# Qwiic_Iridium_9603N.net
KiCad netlist of a schematic drawn in EAGLE
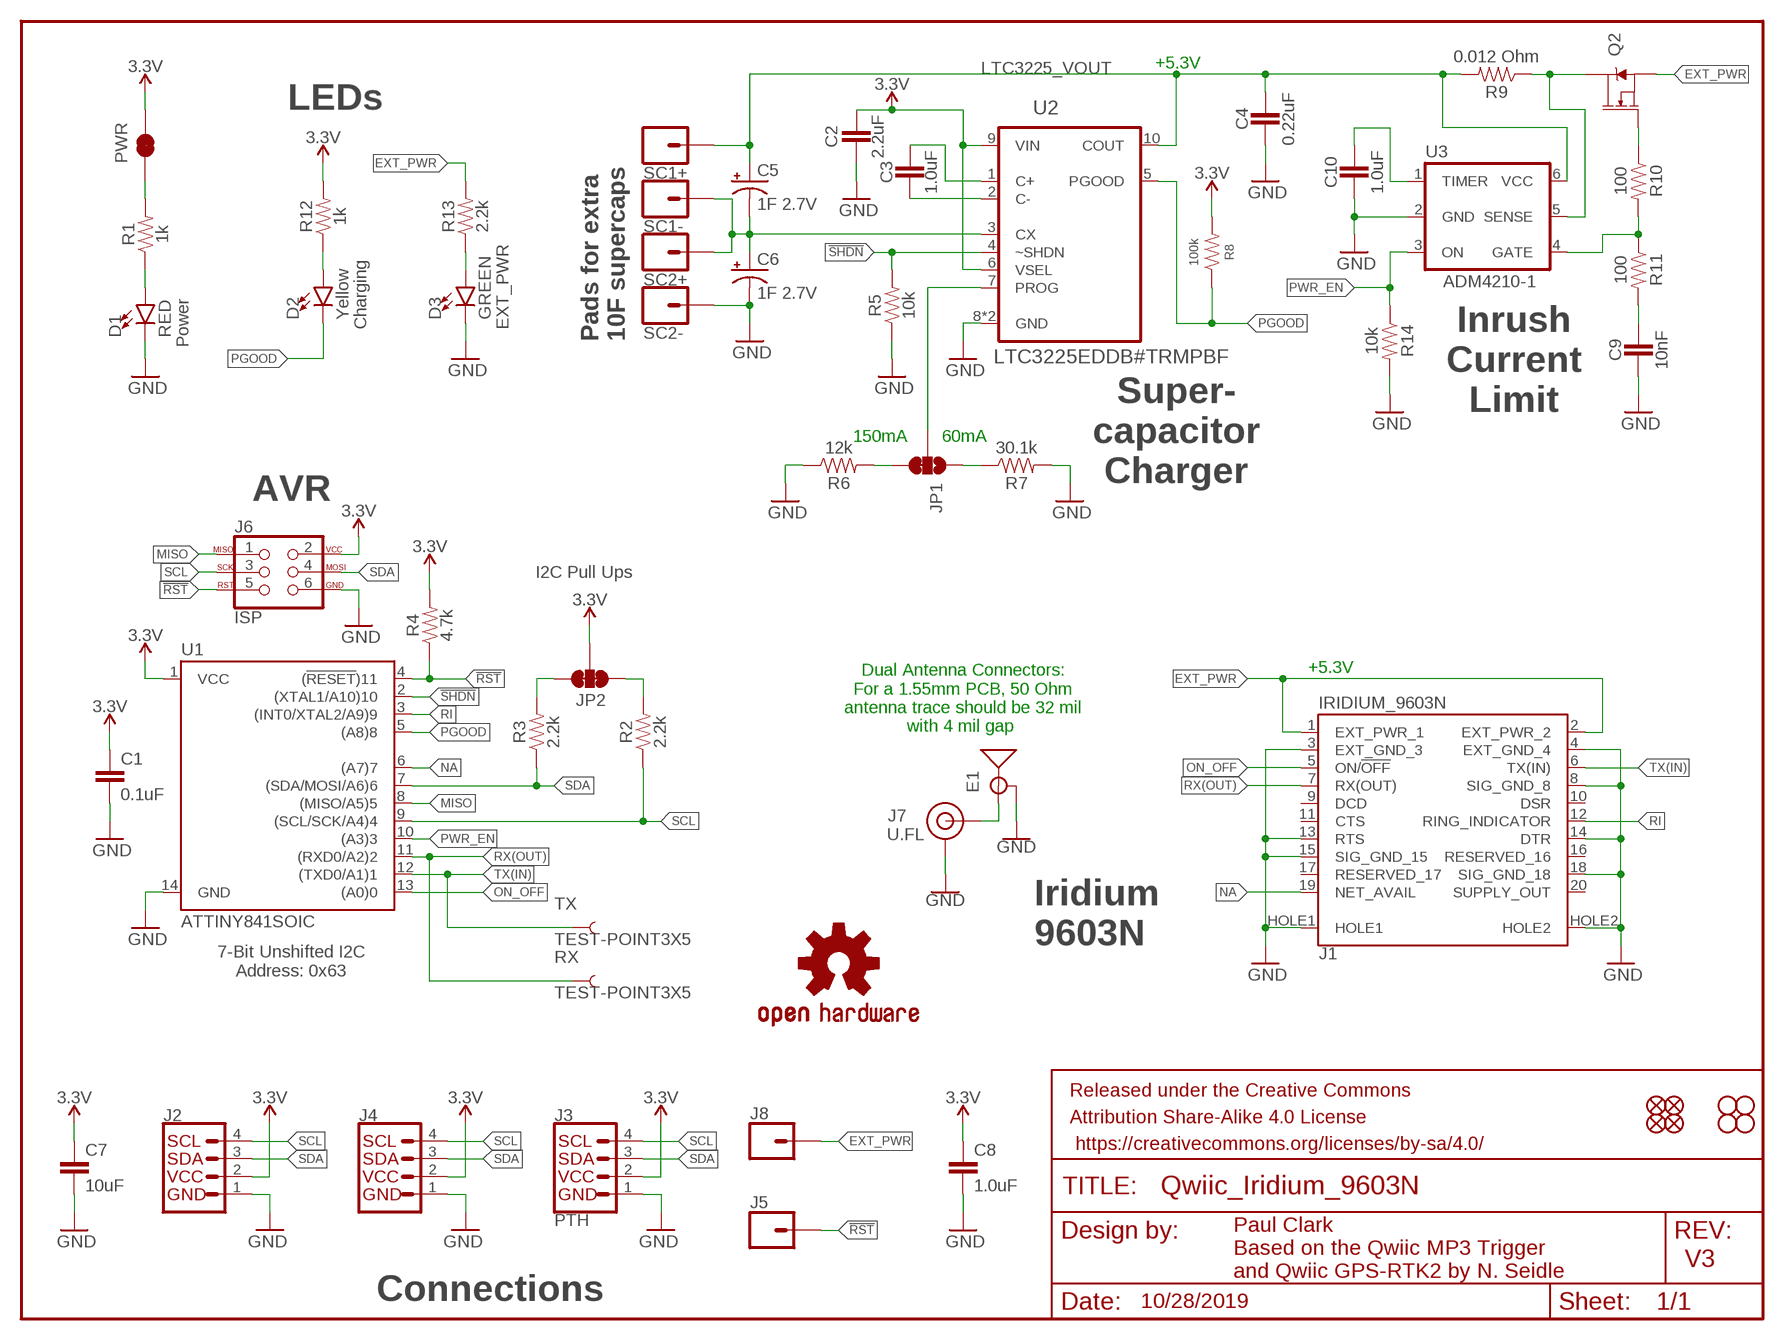
[diagram p0: schematic, sheet 1]

(export (version "E")
  (design (tool "Eeschema 10.0.6"))
  (components
    (comp (ref "C1")
      (value "0.1uF")
      (footprint "eagle-import:0603")
      (libsource (lib "eagle-import") (part "0.1UF-0603-25V-5%"))
    )
    (comp (ref "C2")
      (value "2.2uF")
      (footprint "eagle-import:0603")
      (libsource (lib "eagle-import") (part "2.2UF-0603-10V-20%"))
    )
    (comp (ref "C3")
      (value "1.0uF")
      (footprint "eagle-import:0603")
      (libsource (lib "eagle-import") (part "1.0UF-0603-16V-10%-X7R"))
    )
    (comp (ref "C4")
      (value "0.22uF")
      (footprint "eagle-import:0603")
      (libsource (lib "eagle-import") (part "0.22UF-0603-25V-10%"))
    )
    (comp (ref "C5")
      (value "1F 2.7V")
      (footprint "eagle-import:CPOL-RADIAL-1F-2.7V")
      (libsource (lib "eagle-import") (part "1F-2.7V(PTH)CPOL-RADIAL-1H-2.7V"))
    )
    (comp (ref "C6")
      (value "1F 2.7V")
      (footprint "eagle-import:CPOL-RADIAL-1F-2.7V")
      (libsource (lib "eagle-import") (part "1F-2.7V(PTH)CPOL-RADIAL-1H-2.7V"))
    )
    (comp (ref "C7")
      (value "10uF")
      (footprint "eagle-import:0603")
      (libsource (lib "eagle-import") (part "10UF-0603-6.3V-20%"))
    )
    (comp (ref "C8")
      (value "1.0uF")
      (footprint "eagle-import:0603")
      (libsource (lib "eagle-import") (part "1.0UF-0603-16V-10%-X7R"))
    )
    (comp (ref "C9")
      (value "10nF")
      (footprint "eagle-import:0603")
      (libsource (lib "eagle-import") (part "10NF-0603-50V-10%"))
    )
    (comp (ref "C10")
      (value "1.0uF")
      (footprint "eagle-import:0603")
      (libsource (lib "eagle-import") (part "1.0UF-0603-16V-10%-X7R"))
    )
    (comp (ref "D1")
      (value "RED")
      (footprint "eagle-import:LED-0603")
      (libsource (lib "eagle-import") (part "LED-RED0603"))
    )
    (comp (ref "D2")
      (value "Yellow")
      (footprint "eagle-import:LED-0603")
      (libsource (lib "eagle-import") (part "LED-YELLOW0603"))
    )
    (comp (ref "D3")
      (value "GREEN")
      (footprint "eagle-import:LED-0603")
      (libsource (lib "eagle-import") (part "LED-GREEN0603"))
    )
    (comp (ref "E1")
      (value "ANTENNA-GROUNDEDEDGE_SMA")
      (footprint "eagle-import:SMA-EDGE")
      (libsource (lib "eagle-import") (part "ANTENNA-GROUNDEDEDGE_SMA"))
    )
    (comp (ref "FRAME1")
      (value "FRAME-LETTER")
      (footprint "eagle-import:CREATIVE_COMMONS")
      (libsource (lib "eagle-import") (part "FRAME-LETTER"))
    )
    (comp (ref "J1")
      (value "IRIDIUM_9603N")
      (footprint "eagle-import:IRIDIUM_9603N")
      (libsource (lib "eagle-import") (part "IRIDIUM_9603N"))
    )
    (comp (ref "J2")
      (value "QWIIC_CONNECTORJS-1MM")
      (footprint "eagle-import:JST04_1MM_RA")
      (libsource (lib "eagle-import") (part "QWIIC_CONNECTORJS-1MM"))
    )
    (comp (ref "J3")
      (value "PTH")
      (footprint "eagle-import:1X04_NO_SILK")
      (libsource (lib "eagle-import") (part "I2C_STANDARD_NO_SILK"))
    )
    (comp (ref "J4")
      (value "QWIIC_CONNECTORJS-1MM")
      (footprint "eagle-import:JST04_1MM_RA")
      (libsource (lib "eagle-import") (part "QWIIC_CONNECTORJS-1MM"))
    )
    (comp (ref "J5")
      (value "CONN_01PTH_NO_SILK_YES_STOP")
      (footprint "eagle-import:1X01_NO_SILK")
      (libsource (lib "eagle-import") (part "CONN_01PTH_NO_SILK_YES_STOP"))
    )
    (comp (ref "J6")
      (value "ISP")
      (footprint "eagle-import:2X3_TEST_POINTS")
      (libsource (lib "eagle-import") (part "AVR_SPI_PROG_3X2TESTPOINTS"))
    )
    (comp (ref "J7")
      (value "U.FL")
      (footprint "eagle-import:U.FL")
      (libsource (lib "eagle-import") (part "U.FL2PIN"))
    )
    (comp (ref "J8")
      (value "CONN_01PTH_NO_SILK_YES_STOP")
      (footprint "eagle-import:1X01_NO_SILK")
      (libsource (lib "eagle-import") (part "CONN_01PTH_NO_SILK_YES_STOP"))
    )
    (comp (ref "JP1")
      (value "JUMPER-SMT_3_1-NC_TRACE_SILK")
      (footprint "eagle-import:SMT-JUMPER_3_1-NC_TRACE_SILK")
      (libsource (lib "eagle-import") (part "JUMPER-SMT_3_1-NC_TRACE_SILK"))
    )
    (comp (ref "JP2")
      (value "JUMPER-SMT_3_2-NC_TRACE_SILK")
      (footprint "eagle-import:SMT-JUMPER_3_2-NC_TRACE_SILK")
      (libsource (lib "eagle-import") (part "JUMPER-SMT_3_2-NC_TRACE_SILK"))
    )
    (comp (ref "JP3")
      (value "STAND-OFF")
      (footprint "eagle-import:STAND-OFF")
      (libsource (lib "eagle-import") (part "STAND-OFF"))
    )
    (comp (ref "JP4")
      (value "STAND-OFF")
      (footprint "eagle-import:STAND-OFF")
      (libsource (lib "eagle-import") (part "STAND-OFF"))
    )
    (comp (ref "JP5")
      (value "FIDUCIAL1X2")
      (footprint "eagle-import:FIDUCIAL-1X2")
      (libsource (lib "eagle-import") (part "FIDUCIAL1X2"))
    )
    (comp (ref "JP6")
      (value "FIDUCIAL1X2")
      (footprint "eagle-import:FIDUCIAL-1X2")
      (libsource (lib "eagle-import") (part "FIDUCIAL1X2"))
    )
    (comp (ref "JP7")
      (value "FIDUCIAL1X2")
      (footprint "eagle-import:FIDUCIAL-1X2")
      (libsource (lib "eagle-import") (part "FIDUCIAL1X2"))
    )
    (comp (ref "JP8")
      (value "FIDUCIAL1X2")
      (footprint "eagle-import:FIDUCIAL-1X2")
      (libsource (lib "eagle-import") (part "FIDUCIAL1X2"))
    )
    (comp (ref "JP9")
      (value "STAND-OFF")
      (footprint "eagle-import:STAND-OFF")
      (libsource (lib "eagle-import") (part "STAND-OFF"))
    )
    (comp (ref "JP10")
      (value "STAND-OFF")
      (footprint "eagle-import:STAND-OFF")
      (libsource (lib "eagle-import") (part "STAND-OFF"))
    )
    (comp (ref "LOGO1")
      (value "OSHW-LOGOMINI")
      (footprint "eagle-import:OSHW-LOGO-MINI")
      (libsource (lib "eagle-import") (part "OSHW-LOGOMINI"))
    )
    (comp (ref "PWR")
      (value "JUMPER-SMT_2_NC_TRACE_SILK")
      (footprint "eagle-import:SMT-JUMPER_2_NC_TRACE_SILK")
      (libsource (lib "eagle-import") (part "JUMPER-SMT_2_NC_TRACE_SILK"))
    )
    (comp (ref "Q2")
      (value "5.8A/30V/35mΩ")
      (footprint "eagle-import:SOT23-3")
      (libsource (lib "eagle-import") (part "MOSFET-NCH-AO3404A"))
    )
    (comp (ref "R1")
      (value "1k")
      (footprint "eagle-import:0603")
      (libsource (lib "eagle-import") (part "1KOHM-0603-1/10W-1%"))
    )
    (comp (ref "R2")
      (value "2.2k")
      (footprint "eagle-import:0603")
      (libsource (lib "eagle-import") (part "2.2KOHM-0603-1/10W-1%"))
    )
    (comp (ref "R3")
      (value "2.2k")
      (footprint "eagle-import:0603")
      (libsource (lib "eagle-import") (part "2.2KOHM-0603-1/10W-1%"))
    )
    (comp (ref "R4")
      (value "4.7k")
      (footprint "eagle-import:0603")
      (libsource (lib "eagle-import") (part "4.7KOHM-0603-1/10W-1%"))
    )
    (comp (ref "R5")
      (value "10k")
      (footprint "eagle-import:0603")
      (libsource (lib "eagle-import") (part "10KOHM-0603-1/10W-1%"))
    )
    (comp (ref "R6")
      (value "12k")
      (footprint "eagle-import:0603")
      (libsource (lib "eagle-import") (part "12KOHM-0603-1/10W-1%"))
    )
    (comp (ref "R7")
      (value "30.1k")
      (footprint "eagle-import:0603")
      (libsource (lib "eagle-import") (part "30.1KOHM-0603-1/10W-1%"))
    )
    (comp (ref "R8")
      (value "100k")
      (footprint "eagle-import:0603")
      (libsource (lib "eagle-import") (part "100KOHM-0603-1/10W-1%"))
    )
    (comp (ref "R9")
      (value "0.012 Ohm")
      (footprint "eagle-import:0603")
      (libsource (lib "eagle-import") (part "RESISTOR0603"))
    )
    (comp (ref "R10")
      (value "100")
      (footprint "eagle-import:0603")
      (libsource (lib "eagle-import") (part "100OHM-0603-1/10W-1%"))
    )
    (comp (ref "R11")
      (value "100")
      (footprint "eagle-import:0603")
      (libsource (lib "eagle-import") (part "100OHM-0603-1/10W-1%"))
    )
    (comp (ref "R12")
      (value "1k")
      (footprint "eagle-import:0603")
      (libsource (lib "eagle-import") (part "1KOHM-0603-1/10W-1%"))
    )
    (comp (ref "R13")
      (value "2.2k")
      (footprint "eagle-import:0603")
      (libsource (lib "eagle-import") (part "2.2KOHM-0603-1/10W-1%"))
    )
    (comp (ref "R14")
      (value "10k")
      (footprint "eagle-import:0603")
      (libsource (lib "eagle-import") (part "SparkFun-Resistors_532_10KOHM-0603-1/10W-1%"))
    )
    (comp (ref "RX")
      (value "TEST-POINT3X5")
      (footprint "eagle-import:PAD.03X.05")
      (libsource (lib "eagle-import") (part "TEST-POINT3X5"))
    )
    (comp (ref "SC1+")
      (value "CONN_01PTH_NO_SILK_YES_STOP")
      (footprint "eagle-import:1X01_NO_SILK")
      (libsource (lib "eagle-import") (part "CONN_01PTH_NO_SILK_YES_STOP"))
    )
    (comp (ref "SC1-")
      (value "CONN_01PTH_NO_SILK_YES_STOP")
      (footprint "eagle-import:1X01_NO_SILK")
      (libsource (lib "eagle-import") (part "CONN_01PTH_NO_SILK_YES_STOP"))
    )
    (comp (ref "SC2+")
      (value "CONN_01PTH_NO_SILK_YES_STOP")
      (footprint "eagle-import:1X01_NO_SILK")
      (libsource (lib "eagle-import") (part "CONN_01PTH_NO_SILK_YES_STOP"))
    )
    (comp (ref "SC2-")
      (value "CONN_01PTH_NO_SILK_YES_STOP")
      (footprint "eagle-import:1X01_NO_SILK")
      (libsource (lib "eagle-import") (part "CONN_01PTH_NO_SILK_YES_STOP"))
    )
    (comp (ref "TX")
      (value "TEST-POINT3X5")
      (footprint "eagle-import:PAD.03X.05")
      (libsource (lib "eagle-import") (part "TEST-POINT3X5"))
    )
    (comp (ref "U1")
      (value "ATTINY841SOIC")
      (footprint "eagle-import:ATTINY841")
      (libsource (lib "eagle-import") (part "ATTINY841SOIC"))
    )
    (comp (ref "U2")
      (value "LTC3225EDDB#TRMPBF")
      (footprint "eagle-import:DFN300X200-10L")
      (libsource (lib "eagle-import") (part "LTC3225EDDB-TRMPBFDFN300X200-10L"))
    )
    (comp (ref "U3")
      (value "ADM4210-1")
      (footprint "eagle-import:TSOT6")
      (libsource (lib "eagle-import") (part "ADM4210-1"))
    )
  )
  (nets
    (net (code "1") (name "/LTC3225_VOUT") (class "Default")
      (node (ref "C4") (pin "1") (pinfunction "1_1") (pintype "passive"))
      (node (ref "C5") (pin "+") (pinfunction "+_+") (pintype "passive"))
      (node (ref "R9") (pin "2") (pinfunction "2_2") (pintype "passive"))
      (node (ref "SC1+") (pin "1") (pinfunction "1_1") (pintype "passive"))
      (node (ref "U2") (pin "10") (pinfunction "COUT_10") (pintype "output"))
      (node (ref "U3") (pin "6") (pinfunction "VCC_6") (pintype "power_in"))
    )
    (net (code "2") (name "/~{RST}") (class "Default")
      (node (ref "J5") (pin "1") (pinfunction "1_1") (pintype "passive"))
      (node (ref "J6") (pin "5") (pinfunction "5_5") (pintype "passive"))
      (node (ref "R4") (pin "1") (pinfunction "1_1") (pintype "passive"))
      (node (ref "U1") (pin "4") (pinfunction "(~{RESET})11_4") (pintype "bidirectional"))
    )
    (net (code "3") (name "/~{SHDN}") (class "Default")
      (node (ref "R5") (pin "2") (pinfunction "2_2") (pintype "passive"))
      (node (ref "U1") (pin "2") (pinfunction "(XTAL1/A10)10_2") (pintype "bidirectional"))
      (node (ref "U2") (pin "4") (pinfunction "~{SHDN}_4") (pintype "input"))
    )
    (net (code "4") (name "3.3V") (class "Default")
      (node (ref "C1") (pin "1") (pinfunction "1_1") (pintype "passive"))
      (node (ref "C2") (pin "1") (pinfunction "1_1") (pintype "passive"))
      (node (ref "C7") (pin "1") (pinfunction "1_1") (pintype "passive"))
      (node (ref "C8") (pin "1") (pinfunction "1_1") (pintype "passive"))
      (node (ref "J2") (pin "2") (pinfunction "2_2") (pintype "power_in"))
      (node (ref "J3") (pin "2") (pinfunction "VCC_2") (pintype "power_in"))
      (node (ref "J4") (pin "2") (pinfunction "2_2") (pintype "power_in"))
      (node (ref "J6") (pin "2") (pinfunction "2_2") (pintype "passive"))
      (node (ref "JP2") (pin "2") (pinfunction "2_2") (pintype "passive"))
      (node (ref "PWR") (pin "2") (pinfunction "2_2") (pintype "passive"))
      (node (ref "R12") (pin "2") (pinfunction "2_2") (pintype "passive"))
      (node (ref "R4") (pin "2") (pinfunction "2_2") (pintype "passive"))
      (node (ref "R8") (pin "2") (pinfunction "2_2") (pintype "passive"))
      (node (ref "U1") (pin "1") (pinfunction "VCC_1") (pintype "bidirectional"))
      (node (ref "U2") (pin "6") (pinfunction "VSEL_6") (pintype "input"))
      (node (ref "U2") (pin "9") (pinfunction "VIN_9") (pintype "power_in"))
    )
    (net (code "5") (name "EXT_PWR") (class "Default")
      (node (ref "J1") (pin "1") (pinfunction "EXT_PWR_1_1") (pintype "power_in"))
      (node (ref "J1") (pin "2") (pinfunction "EXT_PWR_2_2") (pintype "power_in"))
      (node (ref "J8") (pin "1") (pinfunction "1_1") (pintype "passive"))
      (node (ref "Q2") (pin "2") (pinfunction "S_2") (pintype "bidirectional"))
      (node (ref "R13") (pin "2") (pinfunction "2_2") (pintype "passive"))
    )
    (net (code "6") (name "GND") (class "Default")
      (node (ref "C1") (pin "2") (pinfunction "2_2") (pintype "passive"))
      (node (ref "C10") (pin "2") (pinfunction "2_2") (pintype "passive"))
      (node (ref "C2") (pin "2") (pinfunction "2_2") (pintype "passive"))
      (node (ref "C4") (pin "2") (pinfunction "2_2") (pintype "passive"))
      (node (ref "C6") (pin "-") (pinfunction "-_-") (pintype "passive"))
      (node (ref "C7") (pin "2") (pinfunction "2_2") (pintype "passive"))
      (node (ref "C8") (pin "2") (pinfunction "2_2") (pintype "passive"))
      (node (ref "C9") (pin "2") (pinfunction "2_2") (pintype "passive"))
      (node (ref "D1") (pin "C") (pinfunction "C_C") (pintype "passive"))
      (node (ref "D3") (pin "C") (pinfunction "C_C") (pintype "passive"))
      (node (ref "E1") (pin "GND@0") (pinfunction "GND_GND@0") (pintype "bidirectional"))
      (node (ref "E1") (pin "GND@1") (pinfunction "GND_GND@1") (pintype "bidirectional"))
      (node (ref "E1") (pin "GND@2") (pinfunction "GND_GND@2") (pintype "bidirectional"))
      (node (ref "E1") (pin "GND@3") (pinfunction "GND_GND@3") (pintype "bidirectional"))
      (node (ref "J1") (pin "13") (pinfunction "RTS_13") (pintype "input"))
      (node (ref "J1") (pin "14") (pinfunction "DTR_14") (pintype "input"))
      (node (ref "J1") (pin "15") (pinfunction "SIG_GND_15_15") (pintype "power_in"))
      (node (ref "J1") (pin "18") (pinfunction "SIG_GND_18_18") (pintype "power_in"))
      (node (ref "J1") (pin "3") (pinfunction "EXT_GND_3_3") (pintype "power_in"))
      (node (ref "J1") (pin "4") (pinfunction "EXT_GND_4_4") (pintype "power_in"))
      (node (ref "J1") (pin "8") (pinfunction "SIG_GND_8_8") (pintype "power_in"))
      (node (ref "J1") (pin "HOLE1") (pinfunction "HOLE1_HOLE1") (pintype "power_in"))
      (node (ref "J1") (pin "HOLE2") (pinfunction "HOLE2_HOLE2") (pintype "power_in"))
      (node (ref "J2") (pin "1") (pinfunction "1_1") (pintype "power_in"))
      (node (ref "J3") (pin "1") (pinfunction "GND_1") (pintype "power_in"))
      (node (ref "J4") (pin "1") (pinfunction "1_1") (pintype "power_in"))
      (node (ref "J6") (pin "6") (pinfunction "6_6") (pintype "passive"))
      (node (ref "J7") (pin "1") (pinfunction "GND_1") (pintype "bidirectional"))
      (node (ref "J7") (pin "2") (pinfunction "GND_2") (pintype "bidirectional"))
      (node (ref "R14") (pin "2") (pinfunction "2_2") (pintype "passive"))
      (node (ref "R5") (pin "1") (pinfunction "1_1") (pintype "passive"))
      (node (ref "R6") (pin "1") (pinfunction "1_1") (pintype "passive"))
      (node (ref "R7") (pin "2") (pinfunction "2_2") (pintype "passive"))
      (node (ref "SC2-") (pin "1") (pinfunction "1_1") (pintype "passive"))
      (node (ref "U1") (pin "14") (pinfunction "GND_14") (pintype "bidirectional"))
      (node (ref "U2") (pin "11") (pinfunction "GND_11") (pintype "passive"))
      (node (ref "U2") (pin "8") (pinfunction "GND_8") (pintype "passive"))
      (node (ref "U3") (pin "2") (pinfunction "GND_2") (pintype "power_in"))
    )
    (net (code "7") (name "MISO") (class "Default")
      (node (ref "J6") (pin "1") (pinfunction "1_1") (pintype "passive"))
      (node (ref "U1") (pin "8") (pinfunction "(MISO/A5)5_8") (pintype "bidirectional"))
    )
    (net (code "8") (name "NA") (class "Default")
      (node (ref "J1") (pin "19") (pinfunction "NET_AVAIL_19") (pintype "output"))
      (node (ref "U1") (pin "6") (pinfunction "(A7)7_6") (pintype "bidirectional"))
    )
    (net (code "9") (name "Net-(C9-Pad1)") (class "Default")
      (node (ref "C9") (pin "1") (pinfunction "1_1") (pintype "passive"))
      (node (ref "R11") (pin "2") (pinfunction "2_2") (pintype "passive"))
    )
    (net (code "10") (name "Net-(D1-PadA)") (class "Default")
      (node (ref "D1") (pin "A") (pinfunction "A_A") (pintype "passive"))
      (node (ref "R1") (pin "1") (pinfunction "1_1") (pintype "passive"))
    )
    (net (code "11") (name "Net-(D2-PadA)") (class "Default")
      (node (ref "D2") (pin "A") (pinfunction "A_A") (pintype "passive"))
      (node (ref "R12") (pin "1") (pinfunction "1_1") (pintype "passive"))
    )
    (net (code "12") (name "Net-(D3-PadA)") (class "Default")
      (node (ref "D3") (pin "A") (pinfunction "A_A") (pintype "passive"))
      (node (ref "R13") (pin "1") (pinfunction "1_1") (pintype "passive"))
    )
    (net (code "13") (name "Net-(E1-SIGNAL)") (class "Default")
      (node (ref "E1") (pin "SIG") (pinfunction "SIGNAL_SIG") (pintype "bidirectional"))
      (node (ref "J7") (pin "FEED") (pinfunction "SIGNAL_FEED") (pintype "bidirectional"))
    )
    (net (code "14") (name "Net-(JP1-Pad1)") (class "Default")
      (node (ref "JP1") (pin "1") (pinfunction "1_1") (pintype "passive"))
      (node (ref "R7") (pin "1") (pinfunction "1_1") (pintype "passive"))
    )
    (net (code "15") (name "Net-(JP1-Pad3)") (class "Default")
      (node (ref "JP1") (pin "3") (pinfunction "3_3") (pintype "passive"))
      (node (ref "R6") (pin "2") (pinfunction "2_2") (pintype "passive"))
    )
    (net (code "16") (name "Net-(JP2-Pad1)") (class "Default")
      (node (ref "JP2") (pin "1") (pinfunction "1_1") (pintype "passive"))
      (node (ref "R2") (pin "2") (pinfunction "2_2") (pintype "passive"))
    )
    (net (code "17") (name "Net-(JP2-Pad3)") (class "Default")
      (node (ref "JP2") (pin "3") (pinfunction "3_3") (pintype "passive"))
      (node (ref "R3") (pin "2") (pinfunction "2_2") (pintype "passive"))
    )
    (net (code "18") (name "Net-(PWR-Pad1)") (class "Default")
      (node (ref "PWR") (pin "1") (pinfunction "1_1") (pintype "passive"))
      (node (ref "R1") (pin "2") (pinfunction "2_2") (pintype "passive"))
    )
    (net (code "19") (name "Net-(Q2-D)") (class "Default")
      (node (ref "Q2") (pin "3") (pinfunction "D_3") (pintype "bidirectional"))
      (node (ref "R9") (pin "1") (pinfunction "1_1") (pintype "passive"))
      (node (ref "U3") (pin "5") (pinfunction "SENSE_5") (pintype "input"))
    )
    (net (code "20") (name "Net-(Q2-G)") (class "Default")
      (node (ref "Q2") (pin "1") (pinfunction "G_1") (pintype "bidirectional"))
      (node (ref "R10") (pin "1") (pinfunction "1_1") (pintype "passive"))
    )
    (net (code "21") (name "Net-(U2-C+)") (class "Default")
      (node (ref "C3") (pin "1") (pinfunction "1_1") (pintype "passive"))
      (node (ref "U2") (pin "1") (pinfunction "C+_1") (pintype "passive"))
    )
    (net (code "22") (name "Net-(U2-C-)") (class "Default")
      (node (ref "C3") (pin "2") (pinfunction "2_2") (pintype "passive"))
      (node (ref "U2") (pin "2") (pinfunction "C-_2") (pintype "passive"))
    )
    (net (code "23") (name "Net-(U2-CX)") (class "Default")
      (node (ref "C5") (pin "-") (pinfunction "-_-") (pintype "passive"))
      (node (ref "C6") (pin "+") (pinfunction "+_+") (pintype "passive"))
      (node (ref "SC1-") (pin "1") (pinfunction "1_1") (pintype "passive"))
      (node (ref "SC2+") (pin "1") (pinfunction "1_1") (pintype "passive"))
      (node (ref "U2") (pin "3") (pinfunction "CX_3") (pintype "passive"))
    )
    (net (code "24") (name "Net-(U2-PROG)") (class "Default")
      (node (ref "JP1") (pin "2") (pinfunction "2_2") (pintype "passive"))
      (node (ref "U2") (pin "7") (pinfunction "PROG_7") (pintype "input"))
    )
    (net (code "25") (name "Net-(U3-GATE)") (class "Default")
      (node (ref "R10") (pin "2") (pinfunction "2_2") (pintype "passive"))
      (node (ref "R11") (pin "1") (pinfunction "1_1") (pintype "passive"))
      (node (ref "U3") (pin "4") (pinfunction "GATE_4") (pintype "output"))
    )
    (net (code "26") (name "Net-(U3-TIMER)") (class "Default")
      (node (ref "C10") (pin "1") (pinfunction "1_1") (pintype "passive"))
      (node (ref "U3") (pin "1") (pinfunction "TIMER_1") (pintype "input"))
    )
    (net (code "27") (name "ON_OFF") (class "Default")
      (node (ref "J1") (pin "5") (pinfunction "ON/~{OFF}_5") (pintype "input"))
      (node (ref "U1") (pin "13") (pinfunction "(A0)0_13") (pintype "bidirectional"))
    )
    (net (code "28") (name "PGOOD") (class "Default")
      (node (ref "D2") (pin "C") (pinfunction "C_C") (pintype "passive"))
      (node (ref "R8") (pin "1") (pinfunction "1_1") (pintype "passive"))
      (node (ref "U1") (pin "5") (pinfunction "(A8)8_5") (pintype "bidirectional"))
      (node (ref "U2") (pin "5") (pinfunction "PGOOD_5") (pintype "output"))
    )
    (net (code "29") (name "PWR_EN") (class "Default")
      (node (ref "R14") (pin "1") (pinfunction "1_1") (pintype "passive"))
      (node (ref "U1") (pin "10") (pinfunction "(A3)3_10") (pintype "bidirectional"))
      (node (ref "U3") (pin "3") (pinfunction "ON_3") (pintype "input"))
    )
    (net (code "30") (name "RI") (class "Default")
      (node (ref "J1") (pin "12") (pinfunction "RING_INDICATOR_12") (pintype "output"))
      (node (ref "U1") (pin "3") (pinfunction "(INT0/XTAL2/A9)9_3") (pintype "bidirectional"))
    )
    (net (code "31") (name "RX(OUT)") (class "Default")
      (node (ref "J1") (pin "7") (pinfunction "RX(OUT)_7") (pintype "output"))
      (node (ref "RX") (pin "P$1") (pinfunction "1_P$1") (pintype "bidirectional"))
      (node (ref "U1") (pin "11") (pinfunction "(RXD0/A2)2_11") (pintype "bidirectional"))
    )
    (net (code "32") (name "SCL") (class "Default")
      (node (ref "J2") (pin "4") (pinfunction "4_4") (pintype "passive"))
      (node (ref "J3") (pin "4") (pinfunction "SCL_4") (pintype "passive"))
      (node (ref "J4") (pin "4") (pinfunction "4_4") (pintype "passive"))
      (node (ref "J6") (pin "3") (pinfunction "3_3") (pintype "passive"))
      (node (ref "R2") (pin "1") (pinfunction "1_1") (pintype "passive"))
      (node (ref "U1") (pin "9") (pinfunction "(SCL/SCK/A4)4_9") (pintype "bidirectional"))
    )
    (net (code "33") (name "SDA") (class "Default")
      (node (ref "J2") (pin "3") (pinfunction "3_3") (pintype "passive"))
      (node (ref "J3") (pin "3") (pinfunction "SDA_3") (pintype "passive"))
      (node (ref "J4") (pin "3") (pinfunction "3_3") (pintype "passive"))
      (node (ref "J6") (pin "4") (pinfunction "4_4") (pintype "passive"))
      (node (ref "R3") (pin "1") (pinfunction "1_1") (pintype "passive"))
      (node (ref "U1") (pin "7") (pinfunction "(SDA/MOSI/A6)6_7") (pintype "bidirectional"))
    )
    (net (code "34") (name "TX(IN)") (class "Default")
      (node (ref "J1") (pin "6") (pinfunction "TX(IN)_6") (pintype "input"))
      (node (ref "TX") (pin "P$1") (pinfunction "1_P$1") (pintype "bidirectional"))
      (node (ref "U1") (pin "12") (pinfunction "(TXD0/A1)1_12") (pintype "bidirectional"))
    )
    (net (code "35") (name "unconnected-(J1-CTS-Pad11)") (class "Default")
      (node (ref "J1") (pin "11") (pinfunction "CTS_11") (pintype "output"))
    )
    (net (code "36") (name "unconnected-(J1-DCD-Pad9)") (class "Default")
      (node (ref "J1") (pin "9") (pinfunction "DCD_9") (pintype "output"))
    )
    (net (code "37") (name "unconnected-(J1-DSR-Pad10)") (class "Default")
      (node (ref "J1") (pin "10") (pinfunction "DSR_10") (pintype "output"))
    )
    (net (code "38") (name "unconnected-(J1-RESERVED_16-Pad16)") (class "Default")
      (node (ref "J1") (pin "16") (pinfunction "RESERVED_16_16") (pintype "no_connect"))
    )
    (net (code "39") (name "unconnected-(J1-RESERVED_17-Pad17)") (class "Default")
      (node (ref "J1") (pin "17") (pinfunction "RESERVED_17_17") (pintype "no_connect"))
    )
    (net (code "40") (name "unconnected-(J1-SUPPLY_OUT-Pad20)") (class "Default")
      (node (ref "J1") (pin "20") (pinfunction "SUPPLY_OUT_20") (pintype "output"))
    )
  )
)
